# amp_soha_v2.net
KiCad netlist of a schematic drawn in EAGLE
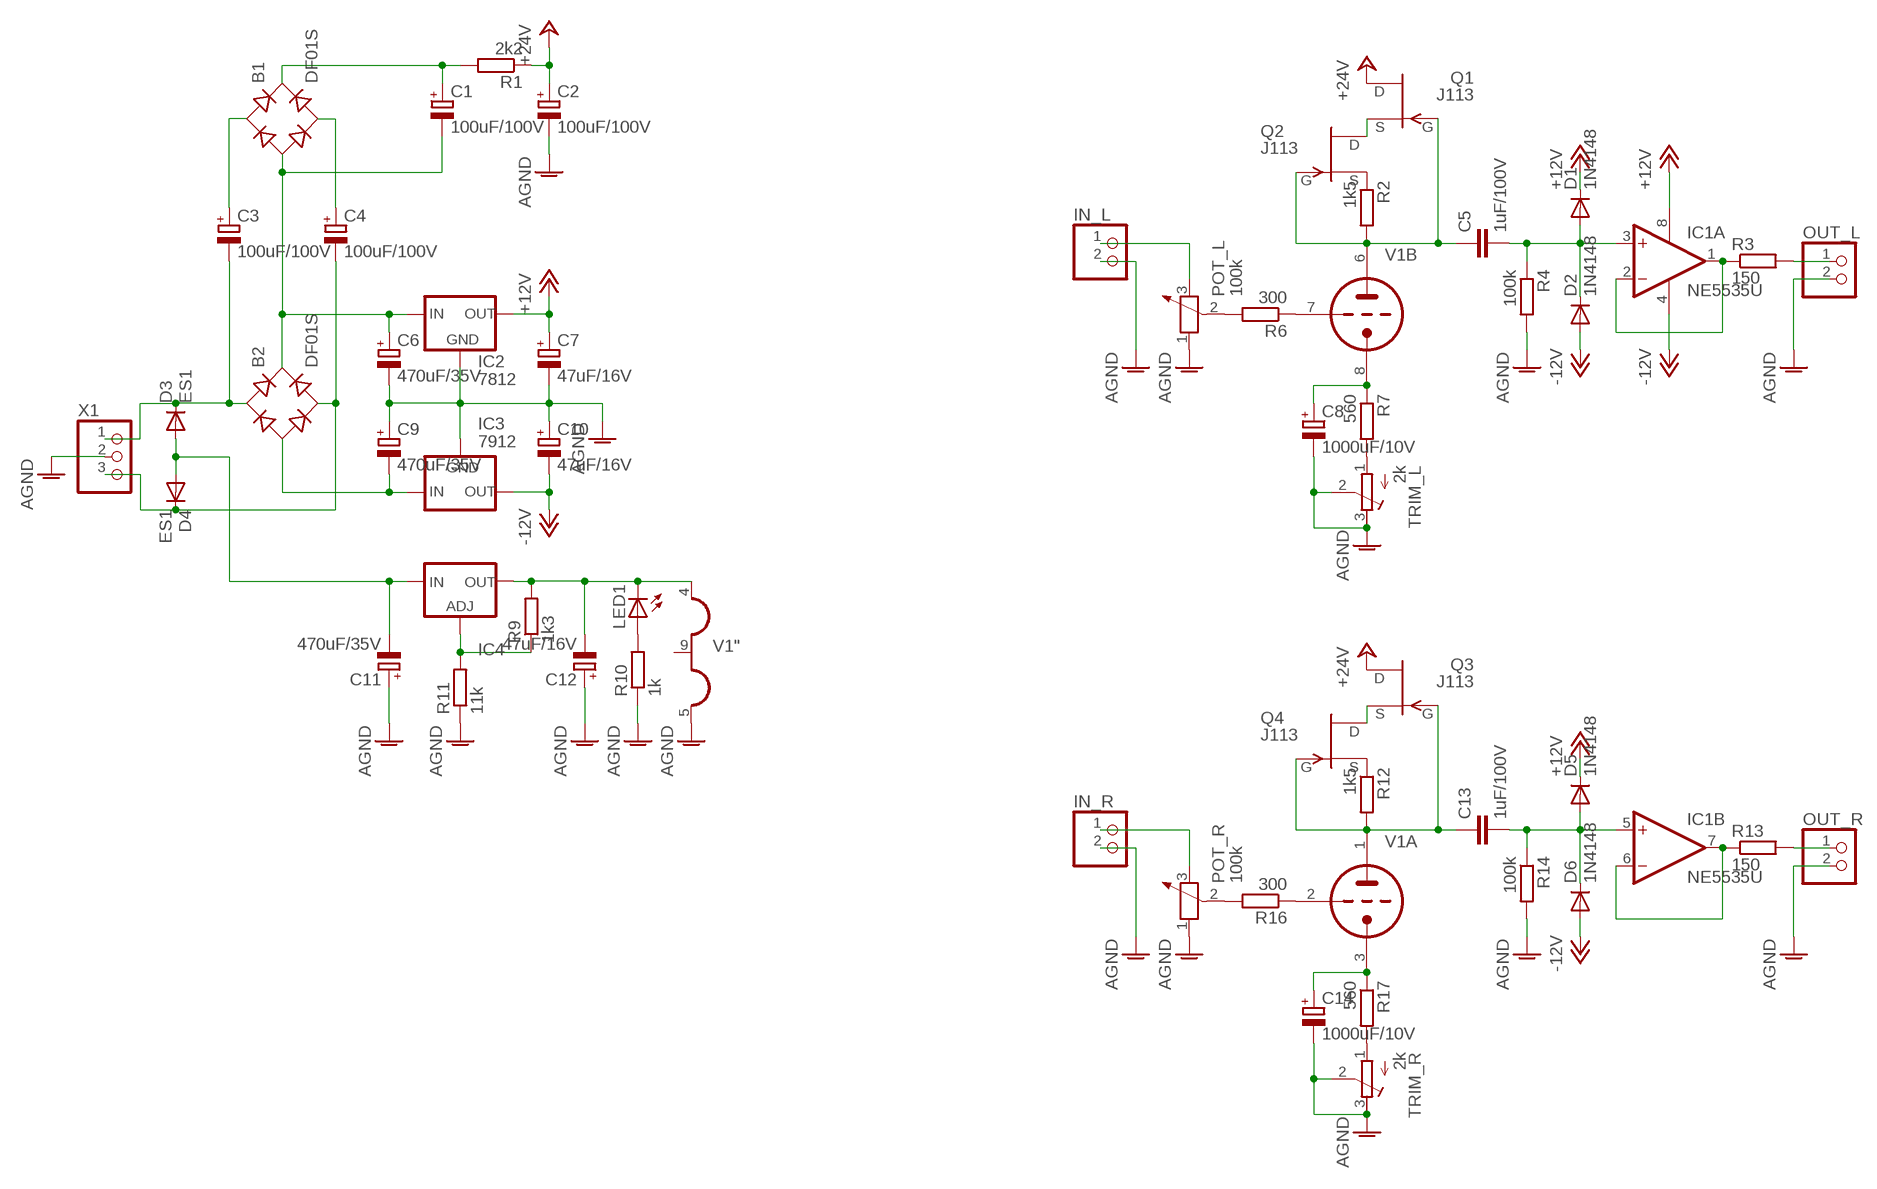
[diagram p0: schematic, sheet 1]

(export (version "E")
  (design (tool "Eeschema 10.0.6"))
  (components
    (comp (ref "B1")
      (value "DF01S")
      (footprint "eagle-import:DFS")
      (libsource (lib "eagle-import") (part "DFS01"))
    )
    (comp (ref "B2")
      (value "DF01S")
      (footprint "eagle-import:DFS")
      (libsource (lib "eagle-import") (part "DFS01"))
    )
    (comp (ref "C1")
      (value "100uF/100V")
      (footprint "eagle-import:E5-10,5")
      (libsource (lib "eagle-import") (part "CPOL-EUE5-10,5"))
    )
    (comp (ref "C2")
      (value "100uF/100V")
      (footprint "eagle-import:E5-10,5")
      (libsource (lib "eagle-import") (part "CPOL-EUE5-10,5"))
    )
    (comp (ref "C3")
      (value "100uF/100V")
      (footprint "eagle-import:E5-10,5")
      (libsource (lib "eagle-import") (part "CPOL-EUE5-10,5"))
    )
    (comp (ref "C4")
      (value "100uF/100V")
      (footprint "eagle-import:E5-10,5")
      (libsource (lib "eagle-import") (part "CPOL-EUE5-10,5"))
    )
    (comp (ref "C5")
      (value "1uF/100V")
      (footprint "eagle-import:C075-052X106")
      (libsource (lib "eagle-import") (part "C-EU075-052X106"))
    )
    (comp (ref "C6")
      (value "470uF/35V")
      (footprint "eagle-import:E5-10,5")
      (libsource (lib "eagle-import") (part "CPOL-EUE5-10,5"))
    )
    (comp (ref "C7")
      (value "47uF/16V")
      (footprint "eagle-import:E2,5-6")
      (libsource (lib "eagle-import") (part "CPOL-EUE2.5-6"))
    )
    (comp (ref "C8")
      (value "1000uF/10V")
      (footprint "eagle-import:E5-10,5")
      (libsource (lib "eagle-import") (part "CPOL-EUE5-10,5"))
    )
    (comp (ref "C9")
      (value "470uF/35V")
      (footprint "eagle-import:E5-10,5")
      (libsource (lib "eagle-import") (part "CPOL-EUE5-10,5"))
    )
    (comp (ref "C10")
      (value "47uF/16V")
      (footprint "eagle-import:E2,5-6")
      (libsource (lib "eagle-import") (part "CPOL-EUE2.5-6"))
    )
    (comp (ref "C11")
      (value "470uF/35V")
      (footprint "eagle-import:E5-10,5")
      (libsource (lib "eagle-import") (part "CPOL-EUE5-10,5"))
    )
    (comp (ref "C12")
      (value "47uF/16V")
      (footprint "eagle-import:E2,5-6")
      (libsource (lib "eagle-import") (part "CPOL-EUE2.5-6"))
    )
    (comp (ref "C13")
      (value "1uF/100V")
      (footprint "eagle-import:C075-052X106")
      (libsource (lib "eagle-import") (part "C-EU075-052X106"))
    )
    (comp (ref "C14")
      (value "1000uF/10V")
      (footprint "eagle-import:E5-10,5")
      (libsource (lib "eagle-import") (part "CPOL-EUE5-10,5"))
    )
    (comp (ref "D1")
      (value "1N4148")
      (footprint "eagle-import:D0805")
      (libsource (lib "eagle-import") (part "1N4148"))
    )
    (comp (ref "D2")
      (value "1N4148")
      (footprint "eagle-import:D0805")
      (libsource (lib "eagle-import") (part "1N4148"))
    )
    (comp (ref "D3")
      (value "ES1")
      (footprint "eagle-import:DO-214AC")
      (libsource (lib "eagle-import") (part "ES1"))
    )
    (comp (ref "D4")
      (value "ES1")
      (footprint "eagle-import:DO-214AC")
      (libsource (lib "eagle-import") (part "ES1"))
    )
    (comp (ref "D5")
      (value "1N4148")
      (footprint "eagle-import:D0805")
      (libsource (lib "eagle-import") (part "1N4148"))
    )
    (comp (ref "D6")
      (value "1N4148")
      (footprint "eagle-import:D0805")
      (libsource (lib "eagle-import") (part "1N4148"))
    )
    (comp (ref "IC1")
      (value "NE5535U")
      (footprint "eagle-import:SO08")
      (libsource (lib "eagle-import") (part "NE5535U"))
    )
    (comp (ref "IC2")
      (value "7812")
      (footprint "eagle-import:78XXS")
      (libsource (lib "eagle-import") (part "78XXTO-220"))
    )
    (comp (ref "IC3")
      (value "7912")
      (footprint "eagle-import:79XXS")
      (libsource (lib "eagle-import") (part "79XXTO-220"))
    )
    (comp (ref "IC4")
      (value "LM337TS")
      (footprint "eagle-import:337TS")
      (libsource (lib "eagle-import") (part "LM337TS"))
    )
    (comp (ref "IN_L")
      (value "PINHD-1X2")
      (footprint "eagle-import:1X02")
      (libsource (lib "eagle-import") (part "PINHD-1X2"))
    )
    (comp (ref "IN_R")
      (value "PINHD-1X2")
      (footprint "eagle-import:1X02")
      (libsource (lib "eagle-import") (part "PINHD-1X2"))
    )
    (comp (ref "LED1")
      (value "LED5MM")
      (footprint "eagle-import:LED5MM")
      (libsource (lib "eagle-import") (part "LED5MM"))
    )
    (comp (ref "OUT_L")
      (value "PINHD-1X2")
      (footprint "eagle-import:1X02")
      (libsource (lib "eagle-import") (part "PINHD-1X2"))
    )
    (comp (ref "OUT_R")
      (value "PINHD-1X2")
      (footprint "eagle-import:1X02")
      (libsource (lib "eagle-import") (part "PINHD-1X2"))
    )
    (comp (ref "POT_L")
      (value "100k")
      (footprint "eagle-import:1X03")
      (libsource (lib "eagle-import") (part "POTENTIOMETER_"))
    )
    (comp (ref "POT_R")
      (value "100k")
      (footprint "eagle-import:1X03")
      (libsource (lib "eagle-import") (part "POTENTIOMETER_"))
    )
    (comp (ref "Q1")
      (value "J113")
      (footprint "eagle-import:TO92")
      (libsource (lib "eagle-import") (part "J113"))
    )
    (comp (ref "Q2")
      (value "J113")
      (footprint "eagle-import:TO92")
      (libsource (lib "eagle-import") (part "J113"))
    )
    (comp (ref "Q3")
      (value "J113")
      (footprint "eagle-import:TO92")
      (libsource (lib "eagle-import") (part "J113"))
    )
    (comp (ref "Q4")
      (value "J113")
      (footprint "eagle-import:TO92")
      (libsource (lib "eagle-import") (part "J113"))
    )
    (comp (ref "R1")
      (value "2k2")
      (footprint "eagle-import:R0805")
      (libsource (lib "eagle-import") (part "R-EU_"))
    )
    (comp (ref "R2")
      (value "1k5")
      (footprint "eagle-import:R0805")
      (libsource (lib "eagle-import") (part "R-EU_"))
    )
    (comp (ref "R3")
      (value "150")
      (footprint "eagle-import:R0805")
      (libsource (lib "eagle-import") (part "R-EU_"))
    )
    (comp (ref "R4")
      (value "100k")
      (footprint "eagle-import:R0805")
      (libsource (lib "eagle-import") (part "R-EU_"))
    )
    (comp (ref "R6")
      (value "300")
      (footprint "eagle-import:R0805")
      (libsource (lib "eagle-import") (part "R-EU_"))
    )
    (comp (ref "R7")
      (value "560")
      (footprint "eagle-import:R0805")
      (libsource (lib "eagle-import") (part "R-EU_"))
    )
    (comp (ref "R9")
      (value "1k3")
      (footprint "eagle-import:R0805")
      (libsource (lib "eagle-import") (part "R-EU_"))
    )
    (comp (ref "R10")
      (value "1k")
      (footprint "eagle-import:R0805")
      (libsource (lib "eagle-import") (part "R-EU_"))
    )
    (comp (ref "R11")
      (value "11k")
      (footprint "eagle-import:R0805")
      (libsource (lib "eagle-import") (part "R-EU_"))
    )
    (comp (ref "R12")
      (value "1k5")
      (footprint "eagle-import:R0805")
      (libsource (lib "eagle-import") (part "R-EU_"))
    )
    (comp (ref "R13")
      (value "150")
      (footprint "eagle-import:R0805")
      (libsource (lib "eagle-import") (part "R-EU_"))
    )
    (comp (ref "R14")
      (value "100k")
      (footprint "eagle-import:R0805")
      (libsource (lib "eagle-import") (part "R-EU_"))
    )
    (comp (ref "R16")
      (value "300")
      (footprint "eagle-import:R0805")
      (libsource (lib "eagle-import") (part "R-EU_"))
    )
    (comp (ref "R17")
      (value "560")
      (footprint "eagle-import:R0805")
      (libsource (lib "eagle-import") (part "R-EU_"))
    )
    (comp (ref "TRIM_L")
      (value "2k")
      (footprint "eagle-import:RTRIM3296W")
      (libsource (lib "eagle-import") (part "RTRIM329W"))
    )
    (comp (ref "TRIM_R")
      (value "2k")
      (footprint "eagle-import:RTRIM3296W")
      (libsource (lib "eagle-import") (part "RTRIM329W"))
    )
    (comp (ref "V1")
      (value "12AU7-P")
      (footprint "eagle-import:NOVAL")
      (libsource (lib "eagle-import") (part "12AU7-P"))
    )
    (comp (ref "X1")
      (value "W237-103")
      (footprint "eagle-import:W237-103")
      (libsource (lib "eagle-import") (part "W237-103"))
    )
  )
  (nets
    (net (code "1") (name "+12V") (class "Default")
      (node (ref "C7") (pin "+") (pinfunction "+_+") (pintype "passive"))
      (node (ref "D1") (pin "K") (pinfunction "C_K") (pintype "passive"))
      (node (ref "D5") (pin "K") (pinfunction "C_K") (pintype "passive"))
      (node (ref "IC1") (pin "8") (pinfunction "V+_8") (pintype "power_in"))
      (node (ref "IC2") (pin "OUT") (pinfunction "OUT_OUT") (pintype "passive"))
    )
    (net (code "2") (name "+24V") (class "Default")
      (node (ref "C2") (pin "+") (pinfunction "+_+") (pintype "passive"))
      (node (ref "Q1") (pin "3") (pinfunction "D_3") (pintype "passive"))
      (node (ref "Q3") (pin "3") (pinfunction "D_3") (pintype "passive"))
      (node (ref "R1") (pin "1") (pinfunction "1_1") (pintype "passive"))
    )
    (net (code "3") (name "-12V") (class "Default")
      (node (ref "C10") (pin "-") (pinfunction "-_-") (pintype "passive"))
      (node (ref "D2") (pin "A") (pinfunction "A_A") (pintype "passive"))
      (node (ref "D6") (pin "A") (pinfunction "A_A") (pintype "passive"))
      (node (ref "IC1") (pin "4") (pinfunction "V-_4") (pintype "power_in"))
      (node (ref "IC3") (pin "OUT") (pinfunction "OUT_OUT") (pintype "passive"))
    )
    (net (code "4") (name "AGND") (class "Default")
      (node (ref "C10") (pin "+") (pinfunction "+_+") (pintype "passive"))
      (node (ref "C11") (pin "+") (pinfunction "+_+") (pintype "passive"))
      (node (ref "C12") (pin "+") (pinfunction "+_+") (pintype "passive"))
      (node (ref "C14") (pin "-") (pinfunction "-_-") (pintype "passive"))
      (node (ref "C2") (pin "-") (pinfunction "-_-") (pintype "passive"))
      (node (ref "C6") (pin "-") (pinfunction "-_-") (pintype "passive"))
      (node (ref "C7") (pin "-") (pinfunction "-_-") (pintype "passive"))
      (node (ref "C8") (pin "-") (pinfunction "-_-") (pintype "passive"))
      (node (ref "C9") (pin "+") (pinfunction "+_+") (pintype "passive"))
      (node (ref "IC2") (pin "GND") (pinfunction "GND_GND") (pintype "input"))
      (node (ref "IC3") (pin "GND") (pinfunction "GND_GND") (pintype "input"))
      (node (ref "IN_L") (pin "2") (pinfunction "2_2") (pintype "passive"))
      (node (ref "IN_R") (pin "2") (pinfunction "2_2") (pintype "passive"))
      (node (ref "OUT_L") (pin "2") (pinfunction "2_2") (pintype "passive"))
      (node (ref "OUT_R") (pin "2") (pinfunction "2_2") (pintype "passive"))
      (node (ref "POT_L") (pin "1") (pinfunction "1_1") (pintype "passive"))
      (node (ref "POT_R") (pin "1") (pinfunction "1_1") (pintype "passive"))
      (node (ref "R10") (pin "1") (pinfunction "1_1") (pintype "passive"))
      (node (ref "R11") (pin "1") (pinfunction "1_1") (pintype "passive"))
      (node (ref "R14") (pin "2") (pinfunction "2_2") (pintype "passive"))
      (node (ref "R4") (pin "2") (pinfunction "2_2") (pintype "passive"))
      (node (ref "TRIM_L") (pin "2") (pinfunction "S_2") (pintype "passive"))
      (node (ref "TRIM_L") (pin "3") (pinfunction "E_3") (pintype "passive"))
      (node (ref "TRIM_R") (pin "2") (pinfunction "S_2") (pintype "passive"))
      (node (ref "TRIM_R") (pin "3") (pinfunction "E_3") (pintype "passive"))
      (node (ref "V1") (pin "5") (pinfunction "H3_5") (pintype "passive"))
      (node (ref "X1") (pin "2") (pinfunction "2_2") (pintype "passive"))
    )
    (net (code "5") (name "Net-(B1-Pad+)") (class "Default")
      (node (ref "B1") (pin "+") (pinfunction "+_+") (pintype "passive"))
      (node (ref "C1") (pin "+") (pinfunction "+_+") (pintype "passive"))
      (node (ref "R1") (pin "2") (pinfunction "2_2") (pintype "passive"))
    )
    (net (code "6") (name "Net-(B1-Pad-)") (class "Default")
      (node (ref "B1") (pin "-") (pinfunction "-_-") (pintype "passive"))
      (node (ref "B2") (pin "+") (pinfunction "+_+") (pintype "passive"))
      (node (ref "C1") (pin "-") (pinfunction "-_-") (pintype "passive"))
      (node (ref "C6") (pin "+") (pinfunction "+_+") (pintype "passive"))
      (node (ref "IC2") (pin "IN") (pinfunction "IN_IN") (pintype "input"))
    )
    (net (code "7") (name "Net-(B1-PadAC1)") (class "Default")
      (node (ref "B1") (pin "AC1") (pinfunction "AC1_AC1") (pintype "passive"))
      (node (ref "C3") (pin "+") (pinfunction "+_+") (pintype "passive"))
    )
    (net (code "8") (name "Net-(B1-PadAC2)") (class "Default")
      (node (ref "B1") (pin "AC2") (pinfunction "AC2_AC2") (pintype "passive"))
      (node (ref "C4") (pin "+") (pinfunction "+_+") (pintype "passive"))
    )
    (net (code "9") (name "Net-(B2-Pad-)") (class "Default")
      (node (ref "B2") (pin "-") (pinfunction "-_-") (pintype "passive"))
      (node (ref "C9") (pin "-") (pinfunction "-_-") (pintype "passive"))
      (node (ref "IC3") (pin "IN") (pinfunction "IN_IN") (pintype "input"))
    )
    (net (code "10") (name "Net-(B2-PadAC1)") (class "Default")
      (node (ref "B2") (pin "AC1") (pinfunction "AC1_AC1") (pintype "passive"))
      (node (ref "C3") (pin "-") (pinfunction "-_-") (pintype "passive"))
      (node (ref "D3") (pin "C") (pinfunction "C_C") (pintype "passive"))
      (node (ref "X1") (pin "1") (pinfunction "1_1") (pintype "passive"))
    )
    (net (code "11") (name "Net-(B2-PadAC2)") (class "Default")
      (node (ref "B2") (pin "AC2") (pinfunction "AC2_AC2") (pintype "passive"))
      (node (ref "C4") (pin "-") (pinfunction "-_-") (pintype "passive"))
      (node (ref "D4") (pin "C") (pinfunction "C_C") (pintype "passive"))
      (node (ref "X1") (pin "3") (pinfunction "3_3") (pintype "passive"))
    )
    (net (code "12") (name "Net-(D2-C)") (class "Default")
      (node (ref "C5") (pin "2") (pinfunction "2_2") (pintype "passive"))
      (node (ref "D1") (pin "A") (pinfunction "A_A") (pintype "passive"))
      (node (ref "D2") (pin "K") (pinfunction "C_K") (pintype "passive"))
      (node (ref "IC1") (pin "3") (pinfunction "+IN_3") (pintype "input"))
      (node (ref "R4") (pin "1") (pinfunction "1_1") (pintype "passive"))
    )
    (net (code "13") (name "Net-(D6-C)") (class "Default")
      (node (ref "C13") (pin "2") (pinfunction "2_2") (pintype "passive"))
      (node (ref "D5") (pin "A") (pinfunction "A_A") (pintype "passive"))
      (node (ref "D6") (pin "K") (pinfunction "C_K") (pintype "passive"))
      (node (ref "IC1") (pin "5") (pinfunction "+IN_5") (pintype "input"))
      (node (ref "R14") (pin "1") (pinfunction "1_1") (pintype "passive"))
    )
    (net (code "14") (name "Net-(IC1A--IN)") (class "Default")
      (node (ref "IC1") (pin "1") (pinfunction "OUT_1") (pintype "output"))
      (node (ref "IC1") (pin "2") (pinfunction "-IN_2") (pintype "input"))
      (node (ref "R3") (pin "1") (pinfunction "1_1") (pintype "passive"))
    )
    (net (code "15") (name "Net-(IC1B--IN)") (class "Default")
      (node (ref "IC1") (pin "6") (pinfunction "-IN_6") (pintype "input"))
      (node (ref "IC1") (pin "7") (pinfunction "OUT_7") (pintype "output"))
      (node (ref "R13") (pin "1") (pinfunction "1_1") (pintype "passive"))
    )
    (net (code "16") (name "Net-(IC4-ADJ)") (class "Default")
      (node (ref "IC4") (pin "1") (pinfunction "ADJ_1") (pintype "input"))
      (node (ref "R11") (pin "2") (pinfunction "2_2") (pintype "passive"))
      (node (ref "R9") (pin "1") (pinfunction "1_1") (pintype "passive"))
    )
    (net (code "17") (name "Net-(IC4-IN)") (class "Default")
      (node (ref "C11") (pin "-") (pinfunction "-_-") (pintype "passive"))
      (node (ref "D3") (pin "A") (pinfunction "A_A") (pintype "passive"))
      (node (ref "D4") (pin "A") (pinfunction "A_A") (pintype "passive"))
      (node (ref "IC4") (pin "2") (pinfunction "IN_2") (pintype "input"))
    )
    (net (code "18") (name "Net-(IC4-OUT)") (class "Default")
      (node (ref "C12") (pin "-") (pinfunction "-_-") (pintype "passive"))
      (node (ref "IC4") (pin "3") (pinfunction "OUT_3") (pintype "passive"))
      (node (ref "LED1") (pin "K") (pinfunction "C_K") (pintype "passive"))
      (node (ref "R9") (pin "2") (pinfunction "2_2") (pintype "passive"))
      (node (ref "V1") (pin "4") (pinfunction "H1_4") (pintype "passive"))
    )
    (net (code "19") (name "Net-(LED1-PadA)") (class "Default")
      (node (ref "LED1") (pin "A") (pinfunction "A_A") (pintype "passive"))
      (node (ref "R10") (pin "2") (pinfunction "2_2") (pintype "passive"))
    )
    (net (code "20") (name "Net-(OUT_L-Pad1)") (class "Default")
      (node (ref "OUT_L") (pin "1") (pinfunction "1_1") (pintype "passive"))
      (node (ref "R3") (pin "2") (pinfunction "2_2") (pintype "passive"))
    )
    (net (code "21") (name "Net-(OUT_R-Pad1)") (class "Default")
      (node (ref "OUT_R") (pin "1") (pinfunction "1_1") (pintype "passive"))
      (node (ref "R13") (pin "2") (pinfunction "2_2") (pintype "passive"))
    )
    (net (code "22") (name "Net-(POT_L-2)") (class "Default")
      (node (ref "IN_L") (pin "1") (pinfunction "1_1") (pintype "passive"))
      (node (ref "POT_L") (pin "3") (pinfunction "2_3") (pintype "passive"))
    )
    (net (code "23") (name "Net-(POT_L-3)") (class "Default")
      (node (ref "POT_L") (pin "2") (pinfunction "3_2") (pintype "passive"))
      (node (ref "R6") (pin "2") (pinfunction "2_2") (pintype "passive"))
    )
    (net (code "24") (name "Net-(POT_R-2)") (class "Default")
      (node (ref "IN_R") (pin "1") (pinfunction "1_1") (pintype "passive"))
      (node (ref "POT_R") (pin "3") (pinfunction "2_3") (pintype "passive"))
    )
    (net (code "25") (name "Net-(POT_R-3)") (class "Default")
      (node (ref "POT_R") (pin "2") (pinfunction "3_2") (pintype "passive"))
      (node (ref "R16") (pin "2") (pinfunction "2_2") (pintype "passive"))
    )
    (net (code "26") (name "Net-(Q1-G)") (class "Default")
      (node (ref "C5") (pin "1") (pinfunction "1_1") (pintype "passive"))
      (node (ref "Q1") (pin "1") (pinfunction "G_1") (pintype "passive"))
      (node (ref "Q2") (pin "1") (pinfunction "G_1") (pintype "passive"))
      (node (ref "R2") (pin "2") (pinfunction "2_2") (pintype "passive"))
      (node (ref "V1") (pin "6") (pinfunction "TA_6") (pintype "passive"))
    )
    (net (code "27") (name "Net-(Q1-S)") (class "Default")
      (node (ref "Q1") (pin "2") (pinfunction "S_2") (pintype "passive"))
      (node (ref "Q2") (pin "3") (pinfunction "D_3") (pintype "passive"))
    )
    (net (code "28") (name "Net-(Q2-S)") (class "Default")
      (node (ref "Q2") (pin "2") (pinfunction "S_2") (pintype "passive"))
      (node (ref "R2") (pin "1") (pinfunction "1_1") (pintype "passive"))
    )
    (net (code "29") (name "Net-(Q3-G)") (class "Default")
      (node (ref "C13") (pin "1") (pinfunction "1_1") (pintype "passive"))
      (node (ref "Q3") (pin "1") (pinfunction "G_1") (pintype "passive"))
      (node (ref "Q4") (pin "1") (pinfunction "G_1") (pintype "passive"))
      (node (ref "R12") (pin "2") (pinfunction "2_2") (pintype "passive"))
      (node (ref "V1") (pin "1") (pinfunction "TA_1") (pintype "passive"))
    )
    (net (code "30") (name "Net-(Q3-S)") (class "Default")
      (node (ref "Q3") (pin "2") (pinfunction "S_2") (pintype "passive"))
      (node (ref "Q4") (pin "3") (pinfunction "D_3") (pintype "passive"))
    )
    (net (code "31") (name "Net-(Q4-S)") (class "Default")
      (node (ref "Q4") (pin "2") (pinfunction "S_2") (pintype "passive"))
      (node (ref "R12") (pin "1") (pinfunction "1_1") (pintype "passive"))
    )
    (net (code "32") (name "Net-(TRIM_L-A)") (class "Default")
      (node (ref "R7") (pin "2") (pinfunction "2_2") (pintype "passive"))
      (node (ref "TRIM_L") (pin "1") (pinfunction "A_1") (pintype "passive"))
    )
    (net (code "33") (name "Net-(TRIM_R-A)") (class "Default")
      (node (ref "R17") (pin "2") (pinfunction "2_2") (pintype "passive"))
      (node (ref "TRIM_R") (pin "1") (pinfunction "A_1") (pintype "passive"))
    )
    (net (code "34") (name "Net-(V1B-TG)") (class "Default")
      (node (ref "R16") (pin "1") (pinfunction "1_1") (pintype "passive"))
      (node (ref "V1") (pin "2") (pinfunction "TG_2") (pintype "passive"))
    )
    (net (code "35") (name "Net-(V1B-TK)") (class "Default")
      (node (ref "C14") (pin "+") (pinfunction "+_+") (pintype "passive"))
      (node (ref "R17") (pin "1") (pinfunction "1_1") (pintype "passive"))
      (node (ref "V1") (pin "3") (pinfunction "TK_3") (pintype "passive"))
    )
    (net (code "36") (name "Net-(V1C-TG)") (class "Default")
      (node (ref "R6") (pin "1") (pinfunction "1_1") (pintype "passive"))
      (node (ref "V1") (pin "7") (pinfunction "TG_7") (pintype "passive"))
    )
    (net (code "37") (name "Net-(V1C-TK)") (class "Default")
      (node (ref "C8") (pin "+") (pinfunction "+_+") (pintype "passive"))
      (node (ref "R7") (pin "1") (pinfunction "1_1") (pintype "passive"))
      (node (ref "V1") (pin "8") (pinfunction "TK_8") (pintype "passive"))
    )
    (net (code "38") (name "unconnected-(V1A-H2-Pad9)") (class "Default")
      (node (ref "V1") (pin "9") (pinfunction "H2_9") (pintype "passive"))
    )
  )
)
